# usb_32u4_board.net
KiCad netlist of a schematic drawn in EasyEDA
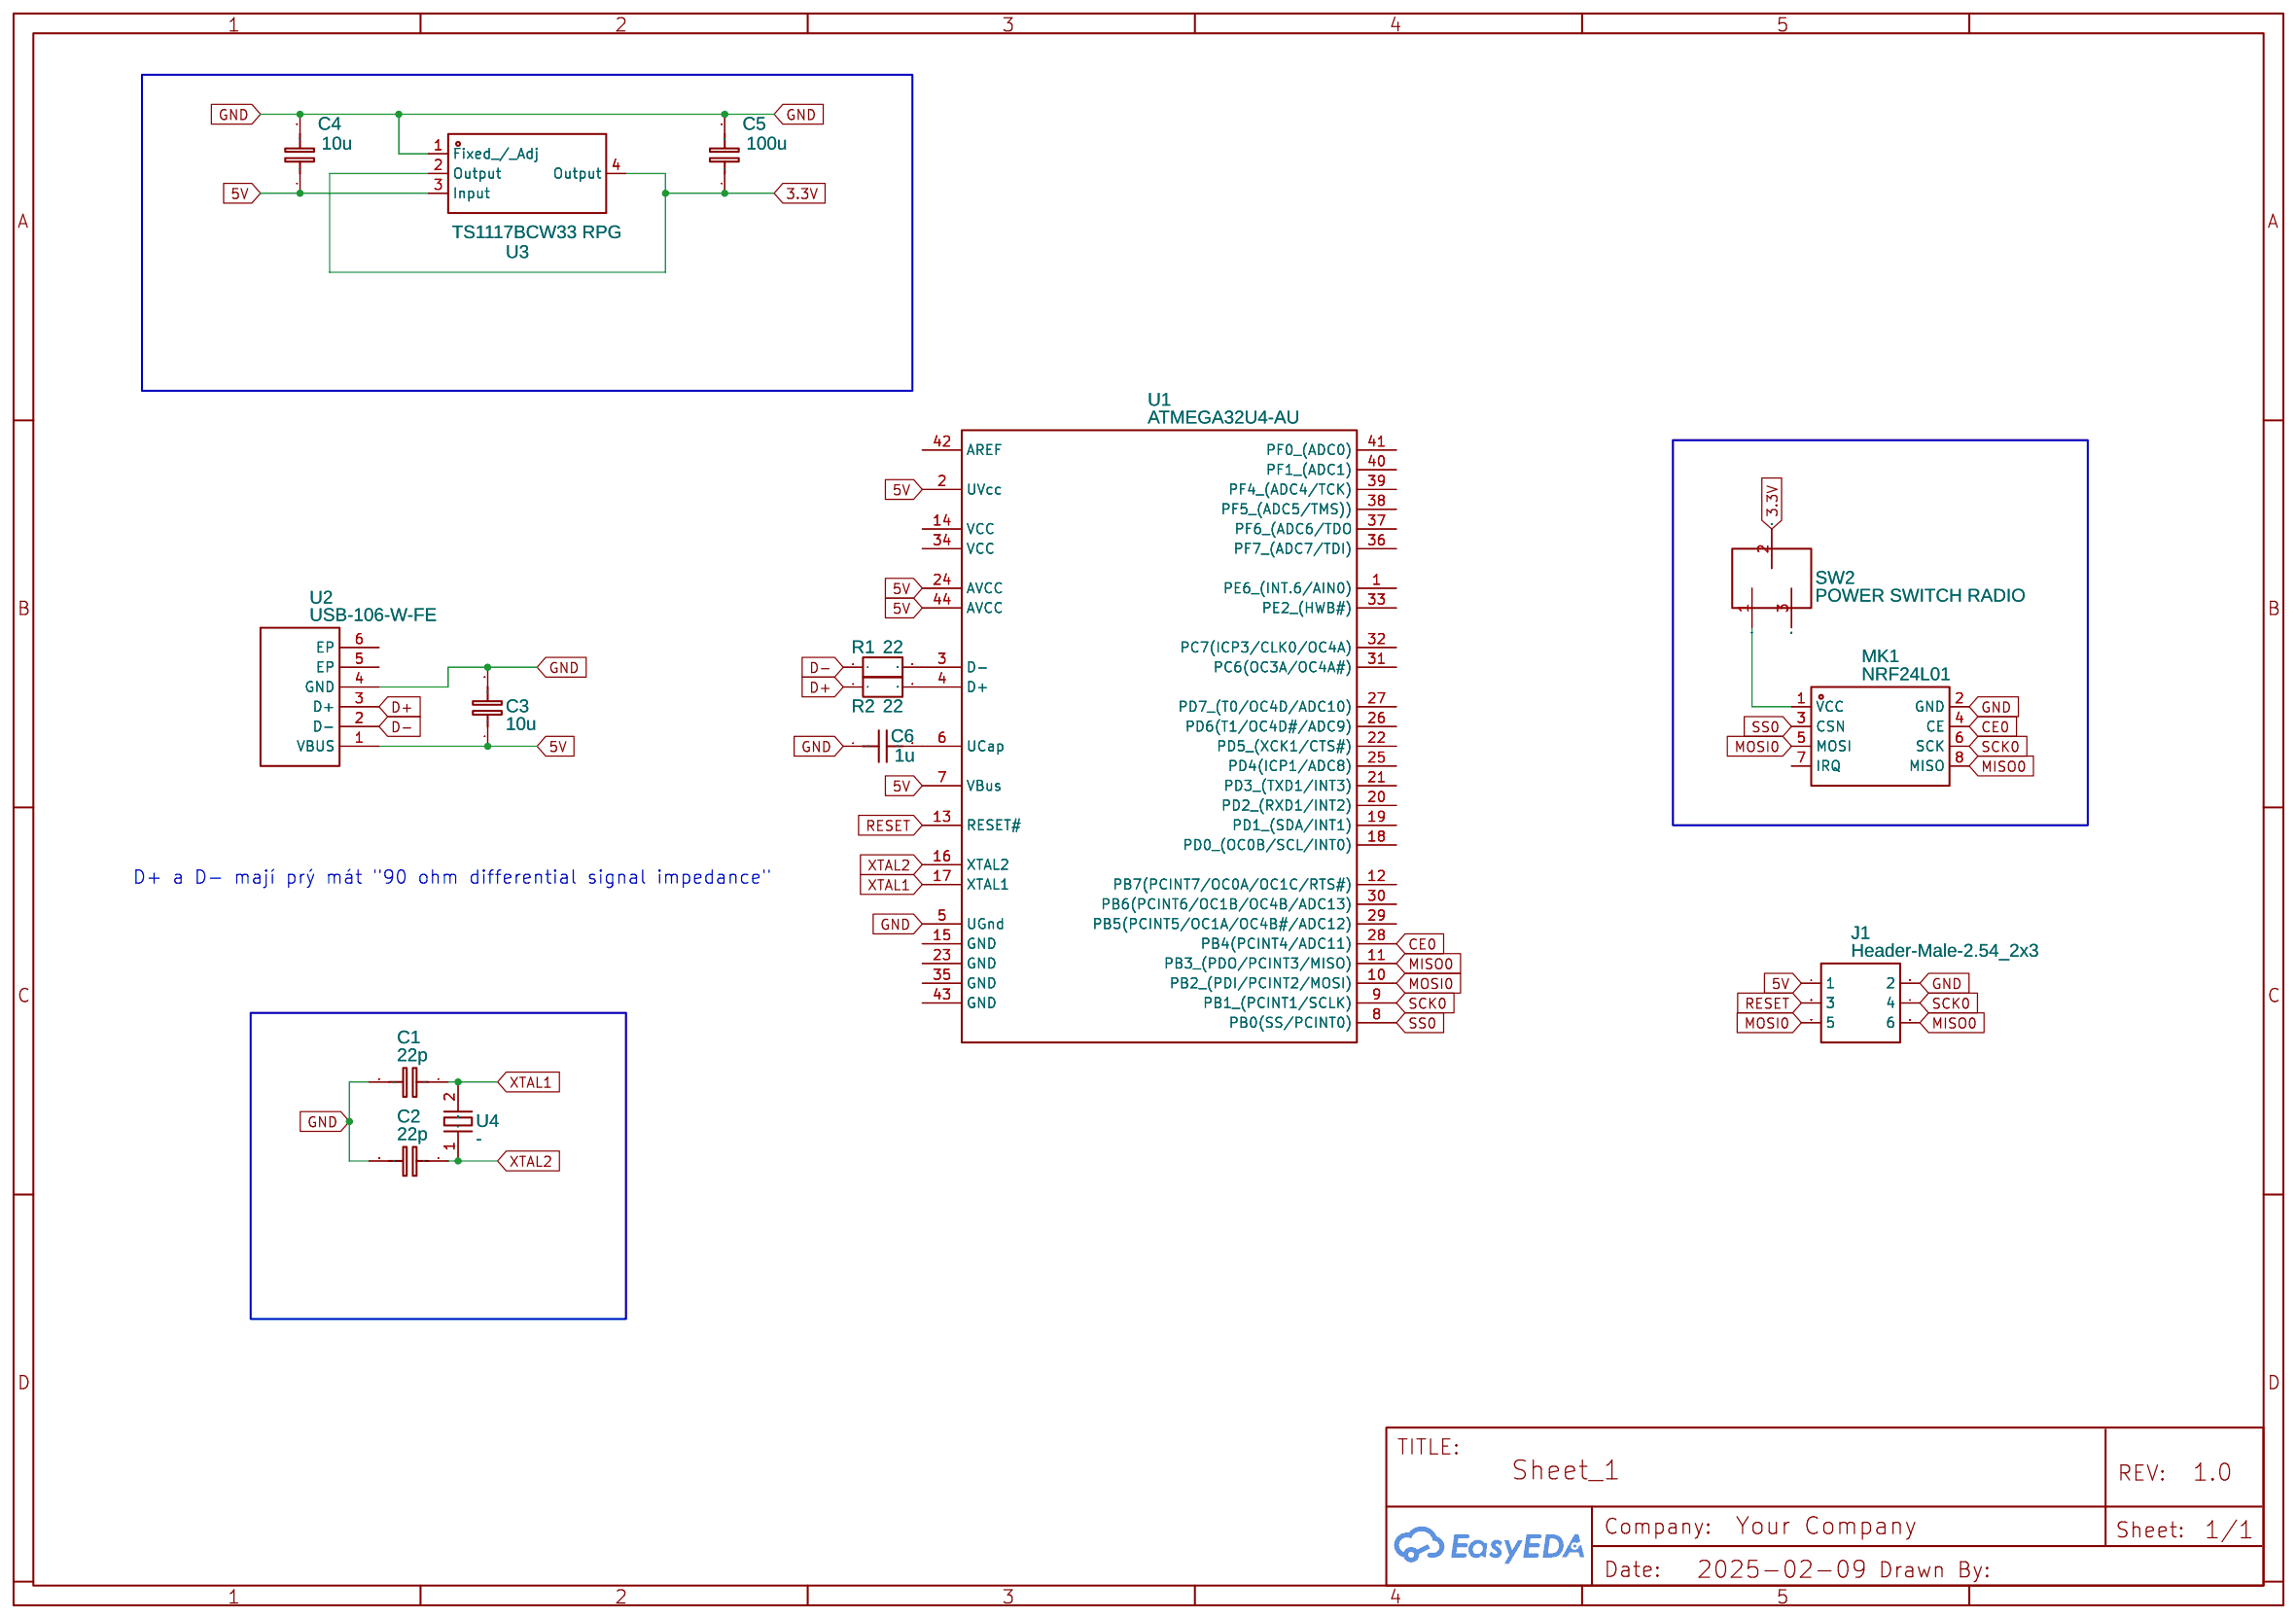
[diagram p0: schematic sheet]

(export (version "E")
  (design (tool "Eeschema 10.0.6"))
  (components
    (comp (ref "C1") (value "22p") (libsource (lib "") (part "C_0603_EU_1")))
    (comp (ref "C2") (value "22p") (libsource (lib "") (part "C_0603_EU_1")))
    (comp (ref "C3") (value "10u") (libsource (lib "") (part "C_0603_EU")))
    (comp (ref "C4") (value "10u") (libsource (lib "") (part "C_0603_EU_2")))
    (comp (ref "C5") (value "100u") (libsource (lib "") (part "C_0603_EU_2")))
    (comp (ref "C6") (value "1u") (libsource (lib "") (part "C_0603_US")))
    (comp (ref "J1")
      (value "Header-Male-2.54_2x3")
      (fields (field (name "Manufacturer Part") "2.54-2*3P针") (field (name "Manufacturer") "BOOMELE(博穆精密)"))
      (libsource (lib "") (part "Header-Male-2.54_2x3"))
    )
    (comp (ref "MK1")
      (value "NRF24L01")
      (fields (field (name "Manufacturer Part") "NF-04") (field (name "Manufacturer") "Ai-Thinker(安信可)"))
      (libsource (lib "") (part "NRF24L01"))
    )
    (comp (ref "R1") (value "22") (libsource (lib "") (part "R_0603_EU")))
    (comp (ref "R2") (value "22") (libsource (lib "") (part "R_0603_EU")))
    (comp (ref "SW2")
      (value "POWER SWITCH RADIO")
      (fields
        (field (name "Manufacturer Part") "DIP switch 8bit,Dip Switch,DSWB03LHGET")
        (field (name "Manufacturer") "KE")
      )
      (libsource (lib "") (part "DIP_SWITCH 3PIN COPY"))
    )
    (comp (ref "U1")
      (value "ATMEGA32U4-AU")
      (fields (field (name "Manufacturer") "MICROCHIP(美国微芯)"))
      (libsource (lib "") (part "ATMEGA32U4-AU"))
    )
    (comp (ref "U2")
      (value "USB-106-W-FE")
      (fields (field (name "Manufacturer") "HOOYA(皓宇电子)"))
      (libsource (lib "") (part "USB-106-W-FE"))
    )
    (comp (ref "U3")
      (value "TS1117BCW33 RPG")
      (fields (field (name "Manufacturer") "Taiwan Semiconductor(台湾半导体)"))
      (libsource (lib "") (part "TS1117BCW33 RPG"))
    )
    (comp (ref "U4")
      (value "-")
      (fields
        (field (name "Manufacturer Part") "CJ03-2211842020A20")
        (field (name "Manufacturer") "CJ(江苏长电/长晶)")
      )
      (libsource (lib "") (part "CJ03-2211842020A20"))
    )
  )
  (nets
    (net (code "1") (name "3.3V") (class "Default")
      (node (ref "C5") (pin "1") (pinfunction "1_1") (pintype "unspecified"))
      (node (ref "SW2") (pin "2") (pinfunction "P2_2") (pintype "unspecified"))
      (node (ref "U3") (pin "2") (pinfunction "Output_2") (pintype "unspecified"))
      (node (ref "U3") (pin "4") (pinfunction "Output_4") (pintype "unspecified"))
    )
    (net (code "2") (name "5V") (class "Default")
      (node (ref "C3") (pin "1") (pinfunction "1_1") (pintype "unspecified"))
      (node (ref "C4") (pin "1") (pinfunction "1_1") (pintype "unspecified"))
      (node (ref "J1") (pin "1") (pinfunction "1_1") (pintype "input"))
      (node (ref "U1") (pin "2") (pinfunction "UVcc_2") (pintype "passive"))
      (node (ref "U1") (pin "24") (pinfunction "AVCC_24") (pintype "passive"))
      (node (ref "U1") (pin "44") (pinfunction "AVCC_44") (pintype "passive"))
      (node (ref "U1") (pin "7") (pinfunction "VBus_7") (pintype "unspecified"))
      (node (ref "U2") (pin "1") (pinfunction "VBUS_1") (pintype "unspecified"))
      (node (ref "U3") (pin "3") (pinfunction "Input_3") (pintype "unspecified"))
    )
    (net (code "3") (name "CE0") (class "Default")
      (node (ref "MK1") (pin "4") (pinfunction "CE_4") (pintype "unspecified"))
      (node (ref "U1") (pin "28") (pinfunction "PB4(PCINT4/ADC11)_28") (pintype "bidirectional"))
    )
    (net (code "4") (name "D+") (class "Default")
      (node (ref "R2") (pin "1") (pinfunction "1_1") (pintype "unspecified"))
      (node (ref "U2") (pin "3") (pinfunction "D+_3") (pintype "unspecified"))
    )
    (net (code "5") (name "D-") (class "Default")
      (node (ref "R1") (pin "1") (pinfunction "1_1") (pintype "unspecified"))
      (node (ref "U2") (pin "2") (pinfunction "D-_2") (pintype "unspecified"))
    )
    (net (code "6") (name "GND") (class "Default")
      (node (ref "C1") (pin "2") (pinfunction "2_2") (pintype "unspecified"))
      (node (ref "C2") (pin "2") (pinfunction "2_2") (pintype "unspecified"))
      (node (ref "C3") (pin "2") (pinfunction "2_2") (pintype "unspecified"))
      (node (ref "C4") (pin "2") (pinfunction "2_2") (pintype "unspecified"))
      (node (ref "C5") (pin "2") (pinfunction "2_2") (pintype "unspecified"))
      (node (ref "C6") (pin "1") (pinfunction "1_1") (pintype "unspecified"))
      (node (ref "J1") (pin "2") (pinfunction "2_2") (pintype "input"))
      (node (ref "MK1") (pin "2") (pinfunction "GND_2") (pintype "unspecified"))
      (node (ref "U1") (pin "5") (pinfunction "UGnd_5") (pintype "passive"))
      (node (ref "U2") (pin "4") (pinfunction "GND_4") (pintype "unspecified"))
      (node (ref "U3") (pin "1") (pinfunction "Fixed_/_Adj_1") (pintype "unspecified"))
    )
    (net (code "7") (name "MISO0") (class "Default")
      (node (ref "J1") (pin "6") (pinfunction "6_6") (pintype "input"))
      (node (ref "MK1") (pin "8") (pinfunction "MISO_8") (pintype "unspecified"))
      (node (ref "U1") (pin "11") (pinfunction "PB3_(PDO/PCINT3/MISO)_11") (pintype "bidirectional"))
    )
    (net (code "8") (name "MOSI0") (class "Default")
      (node (ref "J1") (pin "5") (pinfunction "5_5") (pintype "input"))
      (node (ref "MK1") (pin "5") (pinfunction "MOSI_5") (pintype "unspecified"))
      (node (ref "U1") (pin "10") (pinfunction "PB2_(PDI/PCINT2/MOSI)_10") (pintype "bidirectional"))
    )
    (net (code "9") (name "Net-(U1-D+)") (class "Default")
      (node (ref "R2") (pin "2") (pinfunction "2_2") (pintype "unspecified"))
      (node (ref "U1") (pin "4") (pinfunction "D+_4") (pintype "bidirectional"))
    )
    (net (code "10") (name "Net-(U1-D-)") (class "Default")
      (node (ref "R1") (pin "2") (pinfunction "2_2") (pintype "unspecified"))
      (node (ref "U1") (pin "3") (pinfunction "D-_3") (pintype "bidirectional"))
    )
    (net (code "11") (name "Net-(U1-UCap)") (class "Default")
      (node (ref "C6") (pin "2") (pinfunction "2_2") (pintype "unspecified"))
      (node (ref "U1") (pin "6") (pinfunction "UCap_6") (pintype "unspecified"))
    )
    (net (code "12") (name "RESET") (class "Default")
      (node (ref "J1") (pin "3") (pinfunction "3_3") (pintype "input"))
      (node (ref "U1") (pin "13") (pinfunction "RESET#_13") (pintype "unspecified"))
    )
    (net (code "13") (name "SCK0") (class "Default")
      (node (ref "J1") (pin "4") (pinfunction "4_4") (pintype "input"))
      (node (ref "MK1") (pin "6") (pinfunction "SCK_6") (pintype "unspecified"))
      (node (ref "U1") (pin "9") (pinfunction "PB1_(PCINT1/SCLK)_9") (pintype "bidirectional"))
    )
    (net (code "14") (name "SS0") (class "Default")
      (node (ref "MK1") (pin "3") (pinfunction "CSN_3") (pintype "unspecified"))
      (node (ref "U1") (pin "8") (pinfunction "PB0(SS/PCINT0)_8") (pintype "bidirectional"))
    )
    (net (code "15") (name "XTAL1") (class "Default")
      (node (ref "C1") (pin "1") (pinfunction "1_1") (pintype "unspecified"))
      (node (ref "U1") (pin "17") (pinfunction "XTAL1_17") (pintype "unspecified"))
      (node (ref "U4") (pin "2") (pinfunction "GND_2") (pintype "input"))
    )
    (net (code "16") (name "XTAL2") (class "Default")
      (node (ref "C2") (pin "1") (pinfunction "1_1") (pintype "unspecified"))
      (node (ref "U1") (pin "16") (pinfunction "XTAL2_16") (pintype "output"))
      (node (ref "U4") (pin "1") (pinfunction "1_1") (pintype "input"))
    )
    (net (code "17") (name "unconnected-(MK1-IRQ-Pad7)") (class "Default")
      (node (ref "MK1") (pin "7") (pinfunction "IRQ_7") (pintype "unspecified"))
    )
    (net (code "18") (name "unconnected-(MK1-VCC-Pad1)") (class "Default")
      (node (ref "MK1") (pin "1") (pinfunction "VCC_1") (pintype "unspecified"))
    )
    (net (code "19") (name "unconnected-(SW2-P1-Pad1)") (class "Default")
      (node (ref "SW2") (pin "1") (pinfunction "P1_1") (pintype "unspecified"))
    )
    (net (code "20") (name "unconnected-(SW2-P3-Pad3)") (class "Default")
      (node (ref "SW2") (pin "3") (pinfunction "P3_3") (pintype "unspecified"))
    )
    (net (code "21") (name "unconnected-(U1-AREF-Pad42)") (class "Default")
      (node (ref "U1") (pin "42") (pinfunction "AREF_42") (pintype "unspecified"))
    )
    (net (code "22") (name "unconnected-(U1-GND-Pad15)") (class "Default")
      (node (ref "U1") (pin "15") (pinfunction "GND_15") (pintype "passive"))
    )
    (net (code "23") (name "unconnected-(U1-GND-Pad23)") (class "Default")
      (node (ref "U1") (pin "23") (pinfunction "GND_23") (pintype "passive"))
    )
    (net (code "24") (name "unconnected-(U1-GND-Pad35)") (class "Default")
      (node (ref "U1") (pin "35") (pinfunction "GND_35") (pintype "passive"))
    )
    (net (code "25") (name "unconnected-(U1-GND-Pad43)") (class "Default")
      (node (ref "U1") (pin "43") (pinfunction "GND_43") (pintype "passive"))
    )
    (net (code "26") (name "unconnected-(U1-PB5(PCINT5{slash}OC1A{slash}OC4B#{slash}ADC12)-Pad29)") (class "Default")
      (node (ref "U1") (pin "29") (pinfunction "PB5(PCINT5/OC1A/OC4B#/ADC12)_29") (pintype "bidirectional"))
    )
    (net (code "27") (name "unconnected-(U1-PB6(PCINT6{slash}OC1B{slash}OC4B{slash}ADC13)-Pad30)") (class "Default")
      (node (ref "U1") (pin "30") (pinfunction "PB6(PCINT6/OC1B/OC4B/ADC13)_30") (pintype "bidirectional"))
    )
    (net (code "28") (name "unconnected-(U1-PB7(PCINT7{slash}OC0A{slash}OC1C{slash}RTS#)-Pad12)") (class "Default")
      (node (ref "U1") (pin "12") (pinfunction "PB7(PCINT7/OC0A/OC1C/RTS#)_12") (pintype "bidirectional"))
    )
    (net (code "29") (name "unconnected-(U1-PC6(OC3A{slash}OC4A#)-Pad31)") (class "Default")
      (node (ref "U1") (pin "31") (pinfunction "PC6(OC3A/OC4A#)_31") (pintype "bidirectional"))
    )
    (net (code "30") (name "unconnected-(U1-PC7(ICP3{slash}CLK0{slash}OC4A)-Pad32)") (class "Default")
      (node (ref "U1") (pin "32") (pinfunction "PC7(ICP3/CLK0/OC4A)_32") (pintype "bidirectional"))
    )
    (net (code "31") (name "unconnected-(U1-PD0_(OC0B{slash}SCL{slash}INT0)-Pad18)") (class "Default")
      (node (ref "U1") (pin "18") (pinfunction "PD0_(OC0B/SCL/INT0)_18") (pintype "bidirectional"))
    )
    (net (code "32") (name "unconnected-(U1-PD1_(SDA{slash}INT1)-Pad19)") (class "Default")
      (node (ref "U1") (pin "19") (pinfunction "PD1_(SDA/INT1)_19") (pintype "bidirectional"))
    )
    (net (code "33") (name "unconnected-(U1-PD2_(RXD1{slash}INT2)-Pad20)") (class "Default")
      (node (ref "U1") (pin "20") (pinfunction "PD2_(RXD1/INT2)_20") (pintype "bidirectional"))
    )
    (net (code "34") (name "unconnected-(U1-PD3_(TXD1{slash}INT3)-Pad21)") (class "Default")
      (node (ref "U1") (pin "21") (pinfunction "PD3_(TXD1/INT3)_21") (pintype "bidirectional"))
    )
    (net (code "35") (name "unconnected-(U1-PD4(ICP1{slash}ADC8)-Pad25)") (class "Default")
      (node (ref "U1") (pin "25") (pinfunction "PD4(ICP1/ADC8)_25") (pintype "bidirectional"))
    )
    (net (code "36") (name "unconnected-(U1-PD5_(XCK1{slash}CTS#)-Pad22)") (class "Default")
      (node (ref "U1") (pin "22") (pinfunction "PD5_(XCK1/CTS#)_22") (pintype "bidirectional"))
    )
    (net (code "37") (name "unconnected-(U1-PD6(T1{slash}OC4D#{slash}ADC9)-Pad26)") (class "Default")
      (node (ref "U1") (pin "26") (pinfunction "PD6(T1/OC4D#/ADC9)_26") (pintype "bidirectional"))
    )
    (net (code "38") (name "unconnected-(U1-PD7_(T0{slash}OC4D{slash}ADC10)-Pad27)") (class "Default")
      (node (ref "U1") (pin "27") (pinfunction "PD7_(T0/OC4D/ADC10)_27") (pintype "bidirectional"))
    )
    (net (code "39") (name "unconnected-(U1-PE2_(HWB#)-Pad33)") (class "Default")
      (node (ref "U1") (pin "33") (pinfunction "PE2_(HWB#)_33") (pintype "bidirectional"))
    )
    (net (code "40") (name "unconnected-(U1-PE6_(INT.6{slash}AIN0)-Pad1)") (class "Default")
      (node (ref "U1") (pin "1") (pinfunction "PE6_(INT.6/AIN0)_1") (pintype "bidirectional"))
    )
    (net (code "41") (name "unconnected-(U1-PF0_(ADC0)-Pad41)") (class "Default")
      (node (ref "U1") (pin "41") (pinfunction "PF0_(ADC0)_41") (pintype "bidirectional"))
    )
    (net (code "42") (name "unconnected-(U1-PF1_(ADC1)-Pad40)") (class "Default")
      (node (ref "U1") (pin "40") (pinfunction "PF1_(ADC1)_40") (pintype "bidirectional"))
    )
    (net (code "43") (name "unconnected-(U1-PF4_(ADC4{slash}TCK)-Pad39)") (class "Default")
      (node (ref "U1") (pin "39") (pinfunction "PF4_(ADC4/TCK)_39") (pintype "bidirectional"))
    )
    (net (code "44") (name "unconnected-(U1-PF5_(ADC5{slash}TMS))-Pad38)") (class "Default")
      (node (ref "U1") (pin "38") (pinfunction "PF5_(ADC5/TMS))_38") (pintype "bidirectional"))
    )
    (net (code "45") (name "unconnected-(U1-PF6_(ADC6{slash}TDO-Pad37)") (class "Default")
      (node (ref "U1") (pin "37") (pinfunction "PF6_(ADC6/TDO_37") (pintype "bidirectional"))
    )
    (net (code "46") (name "unconnected-(U1-PF7_(ADC7{slash}TDI)-Pad36)") (class "Default")
      (node (ref "U1") (pin "36") (pinfunction "PF7_(ADC7/TDI)_36") (pintype "bidirectional"))
    )
    (net (code "47") (name "unconnected-(U1-VCC-Pad14)") (class "Default")
      (node (ref "U1") (pin "14") (pinfunction "VCC_14") (pintype "passive"))
    )
    (net (code "48") (name "unconnected-(U1-VCC-Pad34)") (class "Default")
      (node (ref "U1") (pin "34") (pinfunction "VCC_34") (pintype "passive"))
    )
    (net (code "49") (name "unconnected-(U2-EP-Pad5)") (class "Default")
      (node (ref "U2") (pin "5") (pinfunction "EP_5") (pintype "unspecified"))
    )
    (net (code "50") (name "unconnected-(U2-EP-Pad6)") (class "Default")
      (node (ref "U2") (pin "6") (pinfunction "EP_6") (pintype "unspecified"))
    )
  )
)
